# MGT.net
KiCad netlist of a schematic drawn in Altium Designer
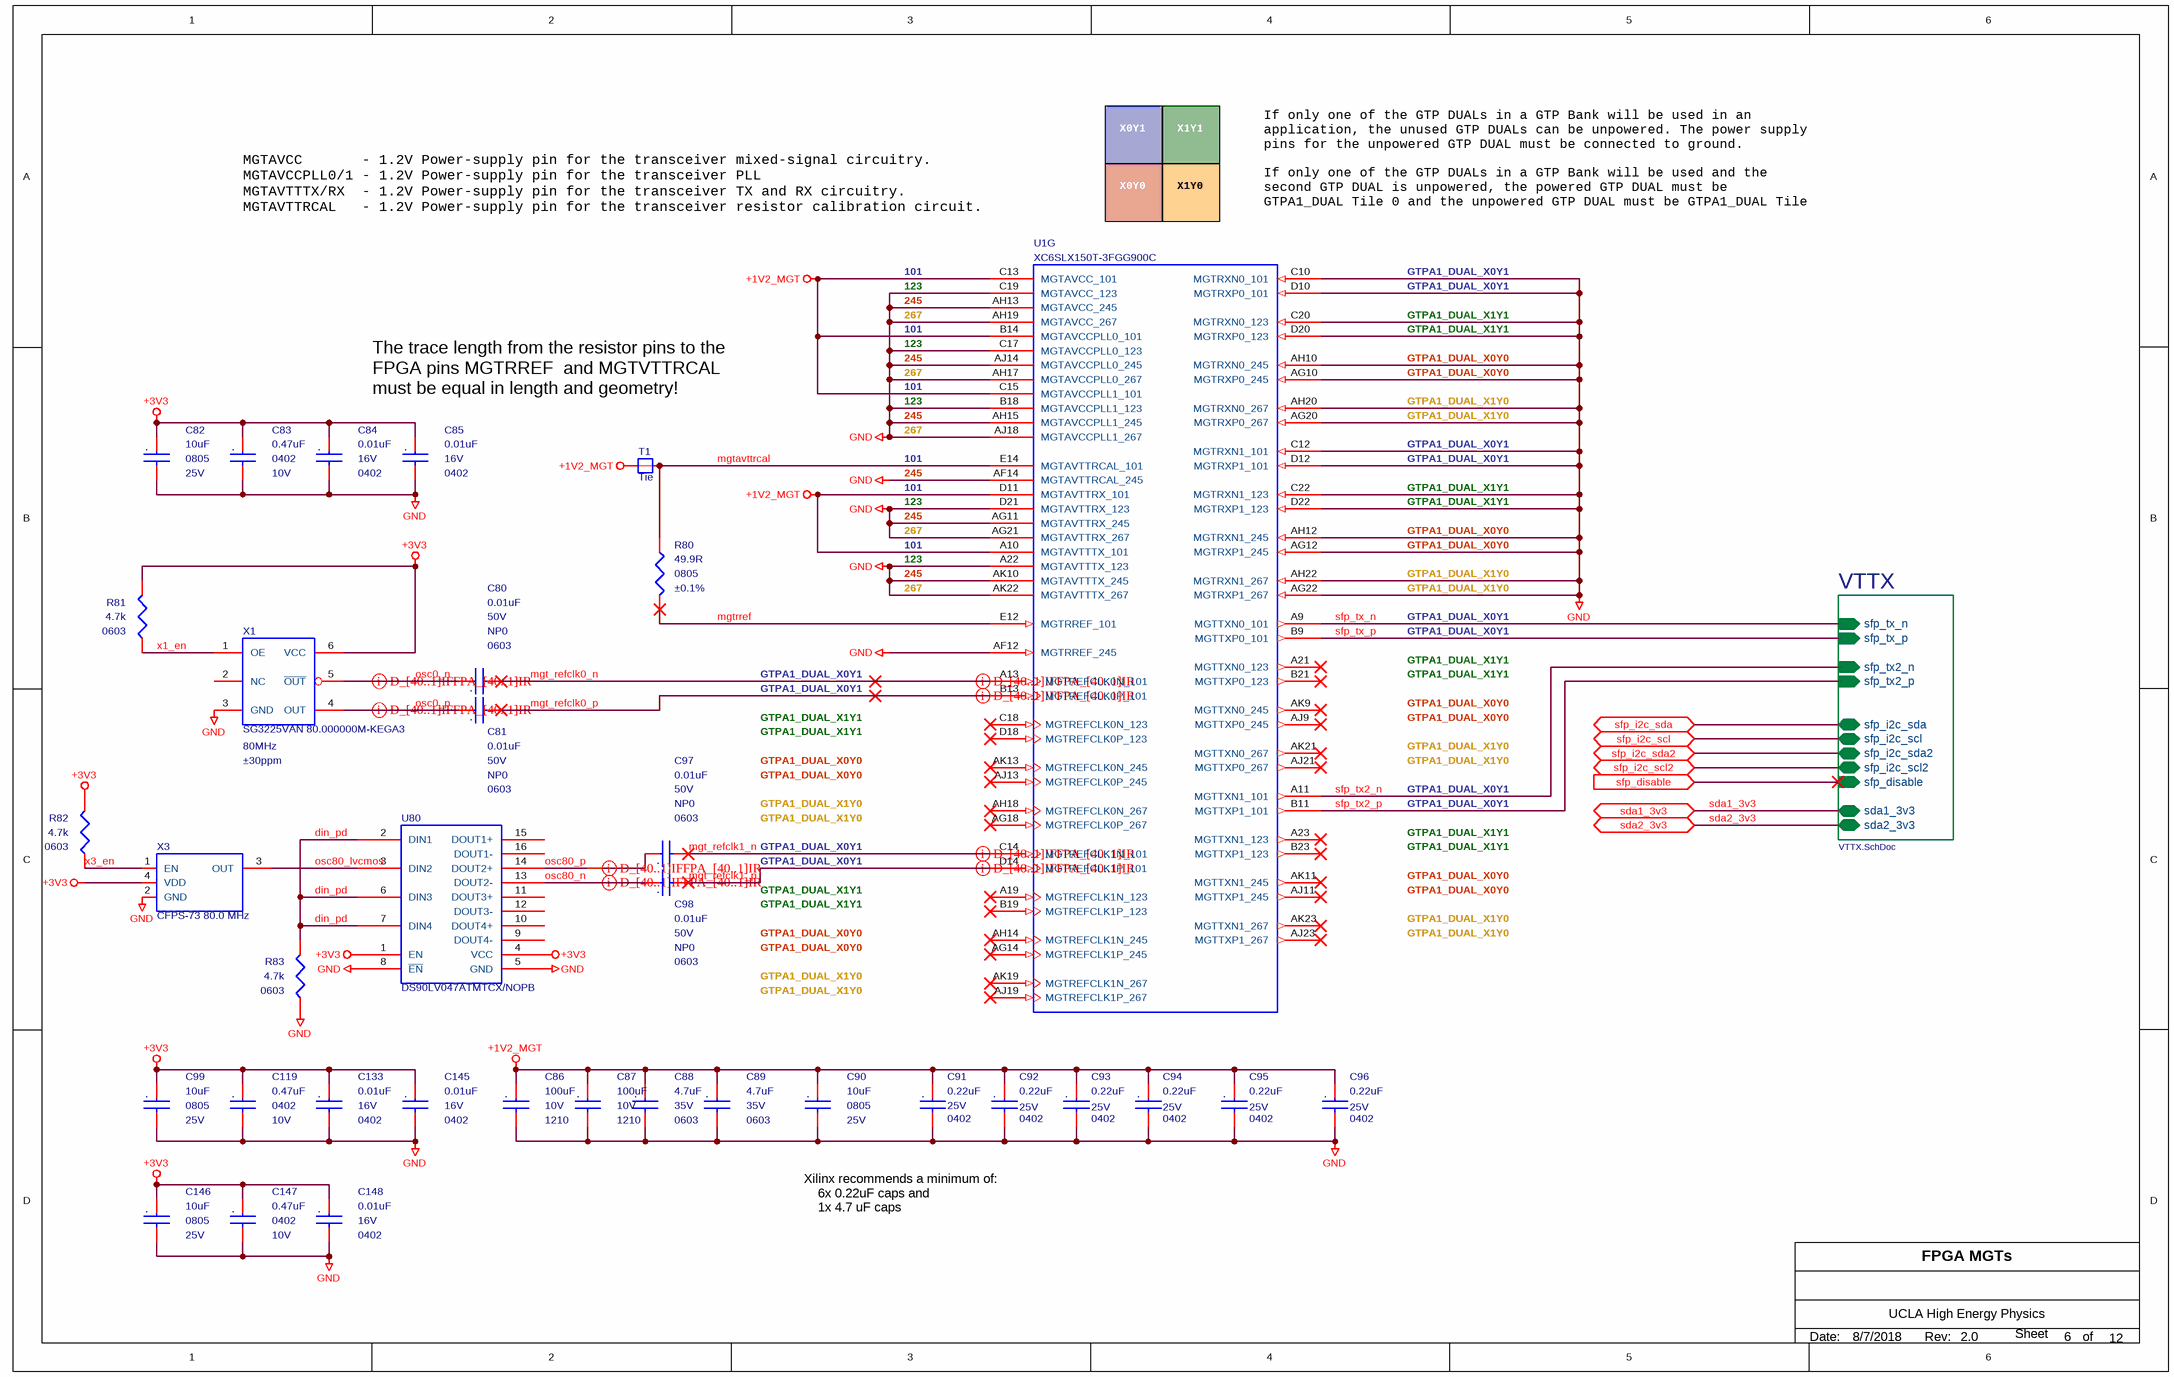
[diagram p0: MGT.SchDoc]

(export (version "E")
  (design (tool "Eeschema 10.0.6"))
  (components
    (comp (ref "C80")
      (value "0.01uF")
      (footprint "MC_S6/SM/C_0603_IPC")
      (description "CAP CER 10000PF 50V NP0 0603")
      (fields
        (field (name "MANUFACTURER") "KEMET")
        (field (name "MANUFACTURER PART NUMBER") "C0603C103J3GACTU")
        (field (name "TEMPERATURE COEFFICIENT") "NP0")
        (field (name "PACKAGE") "0603")
        (field (name "VOLTAGE - RATED") "50V")
      )
      (libsource (lib "ALCT_MEZ_SPARTAN6_Library") (part "C0603C103J3GACTU"))
    )
    (comp (ref "C81")
      (value "0.01uF")
      (footprint "MC_S6/SM/C_0603_IPC")
      (description "CAP CER 10000PF 50V NP0 0603")
      (fields
        (field (name "MANUFACTURER") "KEMET")
        (field (name "MANUFACTURER PART NUMBER") "C0603C103J3GACTU")
        (field (name "TEMPERATURE COEFFICIENT") "NP0")
        (field (name "PACKAGE") "0603")
        (field (name "VOLTAGE - RATED") "50V")
      )
      (libsource (lib "ALCT_MEZ_SPARTAN6_Library") (part "C0603C103J3GACTU"))
    )
    (comp (ref "C82")
      (value "10uF")
      (footprint "MC_S6/SM/C_0805_IPC")
      (description "CAP CER 10UF 25V X5R 0805")
      (fields
        (field (name "MANUFACTURER") "Murata Electronics North America")
        (field (name "MANUFACTURER PART NUMBER") "GRM21BR61E106KA73L")
        (field (name "VOLTAGE - RATED") "25V")
        (field (name "PACKAGE") "0805")
      )
      (libsource (lib "ALCT_MEZ_SPARTAN6_Library") (part "GRM21BR61E106KA73L"))
    )
    (comp (ref "C83")
      (value "0.47uF")
      (footprint "MC_S6/SM/C_0402_IPC")
      (description "CAP CER 0.47UF 10V X5R 0402")
      (fields
        (field (name "MANUFACTURER") "Murata Electronics North America")
        (field (name "MANUFACTURER PART NUMBER") "GRM155R61A474KE15J")
        (field (name "VOLTAGE - RATED") "10V")
        (field (name "PACKAGE") "0402")
      )
      (libsource (lib "ALCT_MEZ_SPARTAN6_Library") (part "GRM155R61A474KE15J"))
    )
    (comp (ref "C84")
      (value "0.01uF")
      (footprint "MC_S6/SM/C_0402_IPC")
      (description "CAP CER 10nF 16V X7R 0402")
      (fields
        (field (name "MANUFACTURER") "KEMET")
        (field (name "MANUFACTURER PART NUMBER") "C0402C103K4RACTU")
        (field (name "VOLTAGE - RATED") "16V")
        (field (name "PACKAGE") "0402")
      )
      (libsource (lib "ALCT_MEZ_SPARTAN6_Library") (part "C0402C103K4RACTU"))
    )
    (comp (ref "C85")
      (value "0.01uF")
      (footprint "MC_S6/SM/C_0402_IPC")
      (description "CAP CER 10nF 16V X7R 0402")
      (fields
        (field (name "MANUFACTURER") "KEMET")
        (field (name "MANUFACTURER PART NUMBER") "C0402C103K4RACTU")
        (field (name "VOLTAGE - RATED") "16V")
        (field (name "PACKAGE") "0402")
      )
      (libsource (lib "ALCT_MEZ_SPARTAN6_Library") (part "C0402C103K4RACTU"))
    )
    (comp (ref "C86")
      (value "100uF")
      (footprint "MC_S6/SM/C_1210_IPC")
      (description "CAP CER 100UF 10V X5R 1210")
      (fields
        (field (name "MANUFACTURER") "Taiyo Yuden")
        (field (name "MANUFACTURER PART NUMBER") "LMK325BJ107MM-T")
        (field (name "VOLTAGE - RATED") "10V")
        (field (name "PACKAGE") "1210")
      )
      (libsource (lib "ALCT_MEZ_SPARTAN6_Library") (part "LMK325BJ107MM-T"))
    )
    (comp (ref "C87")
      (value "100uF")
      (footprint "MC_S6/SM/C_1210_IPC")
      (description "CAP CER 100UF 10V X5R 1210")
      (fields
        (field (name "MANUFACTURER") "Taiyo Yuden")
        (field (name "MANUFACTURER PART NUMBER") "LMK325BJ107MM-T")
        (field (name "VOLTAGE - RATED") "10V")
        (field (name "PACKAGE") "1210")
      )
      (libsource (lib "ALCT_MEZ_SPARTAN6_Library") (part "LMK325BJ107MM-T"))
    )
    (comp (ref "C88")
      (value "4.7uF")
      (footprint "MC_S6/SM/C_0603_IPC")
      (description "CAP CER 4.7UF 35V X5R 0603")
      (fields
        (field (name "MANUFACTURER") "Murata")
        (field (name "MANUFACTURER PART NUMBER") "GRM188R6YA475KE15D")
        (field (name "VOLTAGE - RATED") "35V")
        (field (name "PACKAGE") "0603")
      )
      (libsource (lib "ALCT_MEZ_SPARTAN6_Library") (part "GRM188R6YA475KE15D"))
    )
    (comp (ref "C89")
      (value "4.7uF")
      (footprint "MC_S6/SM/C_0603_IPC")
      (description "CAP CER 4.7UF 35V X5R 0603")
      (fields
        (field (name "MANUFACTURER") "Murata")
        (field (name "MANUFACTURER PART NUMBER") "GRM188R6YA475KE15D")
        (field (name "VOLTAGE - RATED") "35V")
        (field (name "PACKAGE") "0603")
      )
      (libsource (lib "ALCT_MEZ_SPARTAN6_Library") (part "GRM188R6YA475KE15D"))
    )
    (comp (ref "C90")
      (value "10uF")
      (footprint "MC_S6/SM/C_0805_IPC")
      (description "CAP CER 10UF 25V X5R 0805")
      (fields
        (field (name "MANUFACTURER") "Murata Electronics North America")
        (field (name "MANUFACTURER PART NUMBER") "GRM21BR61E106KA73L")
        (field (name "VOLTAGE - RATED") "25V")
        (field (name "PACKAGE") "0805")
      )
      (libsource (lib "ALCT_MEZ_SPARTAN6_Library") (part "GRM21BR61E106KA73L"))
    )
    (comp (ref "C91")
      (value "0.22uF")
      (footprint "MC_S6/SM/C_0402_IPC")
      (description "CAP CER 0.22UF 15V X7R 0402")
      (fields
        (field (name "MANUFACTURER") "Murata Electronics North America")
        (field (name "MANUFACTURER PART NUMBER") "GRM155R71C224KA12D")
        (field (name "VOLTAGE - RATED") "25V")
        (field (name "PACKAGE") "0402")
      )
      (libsource (lib "ALCT_MEZ_SPARTAN6_Library") (part "GRM155R71C224KA12D"))
    )
    (comp (ref "C92")
      (value "0.22uF")
      (footprint "MC_S6/SM/C_0402_IPC")
      (description "CAP CER 0.22UF 15V X7R 0402")
      (fields
        (field (name "MANUFACTURER") "Murata Electronics North America")
        (field (name "MANUFACTURER PART NUMBER") "GRM155R71C224KA12D")
        (field (name "VOLTAGE - RATED") "25V")
        (field (name "PACKAGE") "0402")
      )
      (libsource (lib "ALCT_MEZ_SPARTAN6_Library") (part "GRM155R71C224KA12D"))
    )
    (comp (ref "C93")
      (value "0.22uF")
      (footprint "MC_S6/SM/C_0402_IPC")
      (description "CAP CER 0.22UF 15V X7R 0402")
      (fields
        (field (name "MANUFACTURER") "Murata Electronics North America")
        (field (name "MANUFACTURER PART NUMBER") "GRM155R71C224KA12D")
        (field (name "VOLTAGE - RATED") "25V")
        (field (name "PACKAGE") "0402")
      )
      (libsource (lib "ALCT_MEZ_SPARTAN6_Library") (part "GRM155R71C224KA12D"))
    )
    (comp (ref "C94")
      (value "0.22uF")
      (footprint "MC_S6/SM/C_0402_IPC")
      (description "CAP CER 0.22UF 15V X7R 0402")
      (fields
        (field (name "MANUFACTURER") "Murata Electronics North America")
        (field (name "MANUFACTURER PART NUMBER") "GRM155R71C224KA12D")
        (field (name "VOLTAGE - RATED") "25V")
        (field (name "PACKAGE") "0402")
      )
      (libsource (lib "ALCT_MEZ_SPARTAN6_Library") (part "GRM155R71C224KA12D"))
    )
    (comp (ref "C95")
      (value "0.22uF")
      (footprint "MC_S6/SM/C_0402_IPC")
      (description "CAP CER 0.22UF 15V X7R 0402")
      (fields
        (field (name "MANUFACTURER") "Murata Electronics North America")
        (field (name "MANUFACTURER PART NUMBER") "GRM155R71C224KA12D")
        (field (name "VOLTAGE - RATED") "25V")
        (field (name "PACKAGE") "0402")
      )
      (libsource (lib "ALCT_MEZ_SPARTAN6_Library") (part "GRM155R71C224KA12D"))
    )
    (comp (ref "C96")
      (value "0.22uF")
      (footprint "MC_S6/SM/C_0402_IPC")
      (description "CAP CER 0.22UF 15V X7R 0402")
      (fields
        (field (name "MANUFACTURER") "Murata Electronics North America")
        (field (name "MANUFACTURER PART NUMBER") "GRM155R71C224KA12D")
        (field (name "VOLTAGE - RATED") "25V")
        (field (name "PACKAGE") "0402")
      )
      (libsource (lib "ALCT_MEZ_SPARTAN6_Library") (part "GRM155R71C224KA12D"))
    )
    (comp (ref "C97")
      (value "0.01uF")
      (footprint "MC_S6/SM/C_0603_IPC")
      (description "CAP CER 10000PF 50V NP0 0603")
      (fields
        (field (name "MANUFACTURER") "KEMET")
        (field (name "MANUFACTURER PART NUMBER") "C0603C103J3GACTU")
        (field (name "TEMPERATURE COEFFICIENT") "NP0")
        (field (name "PACKAGE") "0603")
        (field (name "VOLTAGE - RATED") "50V")
      )
      (libsource (lib "ALCT_MEZ_SPARTAN6_Library") (part "C0603C103J3GACTU"))
    )
    (comp (ref "C98")
      (value "0.01uF")
      (footprint "MC_S6/SM/C_0603_IPC")
      (description "CAP CER 10000PF 50V NP0 0603")
      (fields
        (field (name "MANUFACTURER") "KEMET")
        (field (name "MANUFACTURER PART NUMBER") "C0603C103J3GACTU")
        (field (name "TEMPERATURE COEFFICIENT") "NP0")
        (field (name "PACKAGE") "0603")
        (field (name "VOLTAGE - RATED") "50V")
      )
      (libsource (lib "ALCT_MEZ_SPARTAN6_Library") (part "C0603C103J3GACTU"))
    )
    (comp (ref "C99")
      (value "10uF")
      (footprint "MC_S6/SM/C_0805_IPC")
      (description "CAP CER 10UF 25V X5R 0805")
      (fields
        (field (name "MANUFACTURER") "Murata Electronics North America")
        (field (name "MANUFACTURER PART NUMBER") "GRM21BR61E106KA73L")
        (field (name "VOLTAGE - RATED") "25V")
        (field (name "PACKAGE") "0805")
      )
      (libsource (lib "ALCT_MEZ_SPARTAN6_Library") (part "GRM21BR61E106KA73L"))
    )
    (comp (ref "C119")
      (value "0.47uF")
      (footprint "MC_S6/SM/C_0402_IPC")
      (description "CAP CER 0.47UF 10V X5R 0402")
      (fields
        (field (name "MANUFACTURER") "Murata Electronics North America")
        (field (name "MANUFACTURER PART NUMBER") "GRM155R61A474KE15J")
        (field (name "VOLTAGE - RATED") "10V")
        (field (name "PACKAGE") "0402")
      )
      (libsource (lib "ALCT_MEZ_SPARTAN6_Library") (part "GRM155R61A474KE15J"))
    )
    (comp (ref "C133")
      (value "0.01uF")
      (footprint "MC_S6/SM/C_0402_IPC")
      (description "CAP CER 10nF 16V X7R 0402")
      (fields
        (field (name "MANUFACTURER") "KEMET")
        (field (name "MANUFACTURER PART NUMBER") "C0402C103K4RACTU")
        (field (name "VOLTAGE - RATED") "16V")
        (field (name "PACKAGE") "0402")
      )
      (libsource (lib "ALCT_MEZ_SPARTAN6_Library") (part "C0402C103K4RACTU"))
    )
    (comp (ref "C145")
      (value "0.01uF")
      (footprint "MC_S6/SM/C_0402_IPC")
      (description "CAP CER 10nF 16V X7R 0402")
      (fields
        (field (name "MANUFACTURER") "KEMET")
        (field (name "MANUFACTURER PART NUMBER") "C0402C103K4RACTU")
        (field (name "VOLTAGE - RATED") "16V")
        (field (name "PACKAGE") "0402")
      )
      (libsource (lib "ALCT_MEZ_SPARTAN6_Library") (part "C0402C103K4RACTU"))
    )
    (comp (ref "C146")
      (value "10uF")
      (footprint "MC_S6/SM/C_0805_IPC")
      (description "CAP CER 10UF 25V X5R 0805")
      (fields
        (field (name "MANUFACTURER") "Murata Electronics North America")
        (field (name "MANUFACTURER PART NUMBER") "GRM21BR61E106KA73L")
        (field (name "VOLTAGE - RATED") "25V")
        (field (name "PACKAGE") "0805")
      )
      (libsource (lib "ALCT_MEZ_SPARTAN6_Library") (part "GRM21BR61E106KA73L"))
    )
    (comp (ref "C147")
      (value "0.47uF")
      (footprint "MC_S6/SM/C_0402_IPC")
      (description "CAP CER 0.47UF 10V X5R 0402")
      (fields
        (field (name "MANUFACTURER") "Murata Electronics North America")
        (field (name "MANUFACTURER PART NUMBER") "GRM155R61A474KE15J")
        (field (name "VOLTAGE - RATED") "10V")
        (field (name "PACKAGE") "0402")
      )
      (libsource (lib "ALCT_MEZ_SPARTAN6_Library") (part "GRM155R61A474KE15J"))
    )
    (comp (ref "C148")
      (value "0.01uF")
      (footprint "MC_S6/SM/C_0402_IPC")
      (description "CAP CER 10nF 16V X7R 0402")
      (fields
        (field (name "MANUFACTURER") "KEMET")
        (field (name "MANUFACTURER PART NUMBER") "C0402C103K4RACTU")
        (field (name "VOLTAGE - RATED") "16V")
        (field (name "PACKAGE") "0402")
      )
      (libsource (lib "ALCT_MEZ_SPARTAN6_Library") (part "C0402C103K4RACTU"))
    )
    (comp (ref "R80")
      (value "49.9R")
      (footprint "MC_S6/SM/R_0805_IPC")
      (description "RES SMD 49.9 OHM 0.1% 1/8W 0805")
      (fields
        (field (name "MANUFACTURER") "Panasonic Electronic Components")
        (field (name "MANUFACTURER PART NUMBER") "ERA-6AEB49R9V")
        (field (name "TOLERANCE") "±0.1%")
        (field (name "SUPPLIER DEVICE PACKAGE") "0805")
      )
      (libsource (lib "ALCT_MEZ_SPARTAN6_Library") (part "ERA-6AEB49R9V"))
    )
    (comp (ref "R81")
      (value "4.7k")
      (footprint "MC_S6/SM/R_0603_IPC")
      (description "RES SMD 4.7K OHM 1% 1/10W 0603")
      (fields
        (field (name "MANUFACTURER") "Bourns Inc.")
        (field (name "MANUFACTURER PART NUMBER") "CR0603-FX-4701ELF")
        (field (name "SUPPLIER DEVICE PACKAGE") "0603")
      )
      (libsource (lib "ALCT_MEZ_SPARTAN6_Library") (part "CR0603-FX-4701ELF"))
    )
    (comp (ref "R82")
      (value "4.7k")
      (footprint "MC_S6/SM/R_0603_IPC")
      (description "RES SMD 4.7K OHM 1% 1/10W 0603")
      (fields
        (field (name "MANUFACTURER") "Bourns Inc.")
        (field (name "MANUFACTURER PART NUMBER") "CR0603-FX-4701ELF")
        (field (name "SUPPLIER DEVICE PACKAGE") "0603")
      )
      (libsource (lib "ALCT_MEZ_SPARTAN6_Library") (part "CR0603-FX-4701ELF"))
    )
    (comp (ref "R83")
      (value "4.7k")
      (footprint "MC_S6/SM/R_0603_IPC")
      (description "RES SMD 4.7K OHM 1% 1/10W 0603")
      (fields
        (field (name "MANUFACTURER") "Bourns Inc.")
        (field (name "MANUFACTURER PART NUMBER") "CR0603-FX-4701ELF")
        (field (name "SUPPLIER DEVICE PACKAGE") "0603")
      )
      (libsource (lib "ALCT_MEZ_SPARTAN6_Library") (part "CR0603-FX-4701ELF"))
    )
    (comp (ref "T1")
      (value "Tie")
      (footprint "MC_S6/TH/TIE_VIA")
      (libsource (lib "ALCT_MEZ_SPARTAN6_Library") (part "NET TIE VIA"))
    )
    (comp (ref "U1")
      (value "XC6SLX150T-3FGG900C")
      (footprint "MC_S6/BGA/FGG900")
      (fields (field (name "MANUFACTURER") "Xilinx Inc."))
      (libsource (lib "ALCT_MEZ_SPARTAN6_Library") (part "XC6SLX150T-3FGG900C"))
    )
    (comp (ref "U80")
      (value "DS90LV047ATMTCX/NOPB")
      (footprint "MC_S6/SM/TSSOP16")
      (description "IC LINE DVR 3V QUAD DIFF 16TSSOP")
      (fields (field (name "MANUFACTURER") "TI National Semiconductor"))
      (libsource (lib "ALCT_MEZ_SPARTAN6_Library") (part "DS90LV047ATMTCX"))
    )
    (comp (ref "X1")
      (value "SG3225VAN 80.000000M-KEGA3")
      (footprint "MC_S6/SM/XTAL-LVDS-3.2-2.5")
      (description "OSC 80.0000MHZ LVDS SMD")
      (fields
        (field (name "MANUFACTURER") "EPSON")
        (field (name "FREQUENCY") "80MHz")
        (field (name "FREQUENCY STABILITY") "±30ppm")
      )
      (libsource (lib "ALCT_MEZ_SPARTAN6_Library") (part "SG3225VAN 80.000000M-KEGA3"))
    )
    (comp (ref "X3")
      (value "CFPS-73 80.0 MHz")
      (footprint "MC_S6/SM/XTAL-7x5.08")
      (description "XTAL, 80MHz, CMOS")
      (fields
        (field (name "MANUFACTURER") "IQD")
        (field (name "MANUFACTURER PART NUMBER") "LFSPXO009441REEL")
      )
      (libsource (lib "ALCT_MEZ_SPARTAN6_Library") (part "LFSPXO009441"))
    )
  )
  (nets
    (net (code "1") (name "+1V2_MGT") (class "Default")
      (node (ref "C86") (pin "1") (pinfunction "1_1") (pintype "passive"))
      (node (ref "C87") (pin "1") (pinfunction "1_1") (pintype "passive"))
      (node (ref "C88") (pin "1") (pinfunction "1_1") (pintype "passive"))
      (node (ref "C89") (pin "1") (pinfunction "1_1") (pintype "passive"))
      (node (ref "C90") (pin "1") (pinfunction "1_1") (pintype "passive"))
      (node (ref "C91") (pin "1") (pinfunction "1_1") (pintype "passive"))
      (node (ref "C92") (pin "1") (pinfunction "1_1") (pintype "passive"))
      (node (ref "C93") (pin "1") (pinfunction "1_1") (pintype "passive"))
      (node (ref "C94") (pin "1") (pinfunction "1_1") (pintype "passive"))
      (node (ref "C95") (pin "1") (pinfunction "1_1") (pintype "passive"))
      (node (ref "C96") (pin "1") (pinfunction "1_1") (pintype "passive"))
      (node (ref "T1") (pin "2") (pinfunction "2_2") (pintype "passive"))
      (node (ref "U1") (pin "A10") (pinfunction "MGTAVTTTX_101_A10") (pintype "power_in"))
      (node (ref "U1") (pin "B14") (pinfunction "MGTAVCCPLL0_101_B14") (pintype "power_in"))
      (node (ref "U1") (pin "C13") (pinfunction "MGTAVCC_101_C13") (pintype "power_in"))
      (node (ref "U1") (pin "C15") (pinfunction "MGTAVCCPLL1_101_C15") (pintype "power_in"))
      (node (ref "U1") (pin "D11") (pinfunction "MGTAVTTRX_101_D11") (pintype "power_in"))
    )
    (net (code "2") (name "+3V3") (class "Default")
      (node (ref "C119") (pin "1") (pinfunction "1_1") (pintype "passive"))
      (node (ref "C133") (pin "1") (pinfunction "1_1") (pintype "passive"))
      (node (ref "C145") (pin "1") (pinfunction "1_1") (pintype "passive"))
      (node (ref "C146") (pin "1") (pinfunction "1_1") (pintype "passive"))
      (node (ref "C147") (pin "1") (pinfunction "1_1") (pintype "passive"))
      (node (ref "C148") (pin "1") (pinfunction "1_1") (pintype "passive"))
      (node (ref "C82") (pin "1") (pinfunction "1_1") (pintype "passive"))
      (node (ref "C83") (pin "1") (pinfunction "1_1") (pintype "passive"))
      (node (ref "C84") (pin "1") (pinfunction "1_1") (pintype "passive"))
      (node (ref "C85") (pin "1") (pinfunction "1_1") (pintype "passive"))
      (node (ref "C99") (pin "1") (pinfunction "1_1") (pintype "passive"))
      (node (ref "R81") (pin "1") (pinfunction "1_1") (pintype "passive"))
      (node (ref "R82") (pin "1") (pinfunction "1_1") (pintype "passive"))
      (node (ref "U80") (pin "1") (pinfunction "EN_1") (pintype "power_in"))
      (node (ref "U80") (pin "4") (pinfunction "VCC_4") (pintype "power_in"))
      (node (ref "X1") (pin "6") (pinfunction "VCC_6") (pintype "passive"))
      (node (ref "X3") (pin "4") (pinfunction "VDD_4") (pintype "passive"))
    )
    (net (code "3") (name "/din_pd") (class "Default")
      (node (ref "R83") (pin "1") (pinfunction "1_1") (pintype "passive"))
      (node (ref "U80") (pin "2") (pinfunction "DIN1_2") (pintype "power_in"))
      (node (ref "U80") (pin "6") (pinfunction "DIN3_6") (pintype "power_in"))
      (node (ref "U80") (pin "7") (pinfunction "DIN4_7") (pintype "power_in"))
    )
    (net (code "4") (name "/mgt_refclk0_n") (class "Default")
      (node (ref "C80") (pin "2") (pinfunction "2_2") (pintype "passive"))
      (node (ref "U1") (pin "A13") (pinfunction "MGTREFCLK0N_101_A13") (pintype "input"))
    )
    (net (code "5") (name "/mgt_refclk0_p") (class "Default")
      (node (ref "C81") (pin "2") (pinfunction "2_2") (pintype "passive"))
      (node (ref "U1") (pin "B13") (pinfunction "MGTREFCLK0P_101_B13") (pintype "input"))
    )
    (net (code "6") (name "/mgt_refclk1_n") (class "Default")
      (node (ref "C97") (pin "2") (pinfunction "2_2") (pintype "passive"))
      (node (ref "U1") (pin "C14") (pinfunction "MGTREFCLK1N_101_C14") (pintype "input"))
    )
    (net (code "7") (name "/mgt_refclk1_p") (class "Default")
      (node (ref "C98") (pin "2") (pinfunction "2_2") (pintype "passive"))
      (node (ref "U1") (pin "D14") (pinfunction "MGTREFCLK1P_101_D14") (pintype "input"))
    )
    (net (code "8") (name "/mgtavttrcal") (class "Default")
      (node (ref "R80") (pin "1") (pinfunction "1_1") (pintype "passive"))
      (node (ref "T1") (pin "1") (pinfunction "1_1") (pintype "passive"))
      (node (ref "U1") (pin "E14") (pinfunction "MGTAVTTRCAL_101_E14") (pintype "power_in"))
    )
    (net (code "9") (name "/mgtrref") (class "Default")
      (node (ref "R80") (pin "2") (pinfunction "2_2") (pintype "passive"))
      (node (ref "U1") (pin "E12") (pinfunction "MGTRREF_101_E12") (pintype "input"))
    )
    (net (code "10") (name "/osc0_n") (class "Default")
      (node (ref "C80") (pin "1") (pinfunction "1_1") (pintype "passive"))
      (node (ref "X1") (pin "5") (pinfunction "~{OUT}_5") (pintype "passive"))
    )
    (net (code "11") (name "/osc0_p") (class "Default")
      (node (ref "C81") (pin "1") (pinfunction "1_1") (pintype "passive"))
      (node (ref "X1") (pin "4") (pinfunction "OUT_4") (pintype "passive"))
    )
    (net (code "12") (name "/osc80_lvcmos") (class "Default")
      (node (ref "U80") (pin "3") (pinfunction "DIN2_3") (pintype "power_in"))
      (node (ref "X3") (pin "3") (pinfunction "OUT_3") (pintype "passive"))
    )
    (net (code "13") (name "/osc80_n") (class "Default")
      (node (ref "C98") (pin "1") (pinfunction "1_1") (pintype "passive"))
      (node (ref "U80") (pin "13") (pinfunction "DOUT2-_13") (pintype "power_in"))
    )
    (net (code "14") (name "/osc80_p") (class "Default")
      (node (ref "C97") (pin "1") (pinfunction "1_1") (pintype "passive"))
      (node (ref "U80") (pin "14") (pinfunction "DOUT2+_14") (pintype "power_in"))
    )
    (net (code "22") (name "/sfp_tx2_n") (class "Default")
      (node (ref "U1") (pin "A11") (pinfunction "MGTTXN1_101_A11") (pintype "output"))
    )
    (net (code "23") (name "/sfp_tx2_p") (class "Default")
      (node (ref "U1") (pin "B11") (pinfunction "MGTTXP1_101_B11") (pintype "output"))
    )
    (net (code "24") (name "/sfp_tx_n") (class "Default")
      (node (ref "U1") (pin "A9") (pinfunction "MGTTXN0_101_A9") (pintype "output"))
    )
    (net (code "25") (name "/sfp_tx_p") (class "Default")
      (node (ref "U1") (pin "B9") (pinfunction "MGTTXP0_101_B9") (pintype "output"))
    )
    (net (code "26") (name "/x1_en") (class "Default")
      (node (ref "R81") (pin "2") (pinfunction "2_2") (pintype "passive"))
      (node (ref "X1") (pin "1") (pinfunction "OE_1") (pintype "passive"))
    )
    (net (code "27") (name "/x3_en") (class "Default")
      (node (ref "R82") (pin "2") (pinfunction "2_2") (pintype "passive"))
      (node (ref "X3") (pin "1") (pinfunction "EN_1") (pintype "passive"))
    )
    (net (code "28") (name "GND") (class "Default")
      (node (ref "C119") (pin "2") (pinfunction "2_2") (pintype "passive"))
      (node (ref "C133") (pin "2") (pinfunction "2_2") (pintype "passive"))
      (node (ref "C145") (pin "2") (pinfunction "2_2") (pintype "passive"))
      (node (ref "C146") (pin "2") (pinfunction "2_2") (pintype "passive"))
      (node (ref "C147") (pin "2") (pinfunction "2_2") (pintype "passive"))
      (node (ref "C148") (pin "2") (pinfunction "2_2") (pintype "passive"))
      (node (ref "C82") (pin "2") (pinfunction "2_2") (pintype "passive"))
      (node (ref "C83") (pin "2") (pinfunction "2_2") (pintype "passive"))
      (node (ref "C84") (pin "2") (pinfunction "2_2") (pintype "passive"))
      (node (ref "C85") (pin "2") (pinfunction "2_2") (pintype "passive"))
      (node (ref "C86") (pin "2") (pinfunction "2_2") (pintype "passive"))
      (node (ref "C87") (pin "2") (pinfunction "2_2") (pintype "passive"))
      (node (ref "C88") (pin "2") (pinfunction "2_2") (pintype "passive"))
      (node (ref "C89") (pin "2") (pinfunction "2_2") (pintype "passive"))
      (node (ref "C90") (pin "2") (pinfunction "2_2") (pintype "passive"))
      (node (ref "C91") (pin "2") (pinfunction "2_2") (pintype "passive"))
      (node (ref "C92") (pin "2") (pinfunction "2_2") (pintype "passive"))
      (node (ref "C93") (pin "2") (pinfunction "2_2") (pintype "passive"))
      (node (ref "C94") (pin "2") (pinfunction "2_2") (pintype "passive"))
      (node (ref "C95") (pin "2") (pinfunction "2_2") (pintype "passive"))
      (node (ref "C96") (pin "2") (pinfunction "2_2") (pintype "passive"))
      (node (ref "C99") (pin "2") (pinfunction "2_2") (pintype "passive"))
      (node (ref "R83") (pin "2") (pinfunction "2_2") (pintype "passive"))
      (node (ref "U1") (pin "A22") (pinfunction "MGTAVTTTX_123_A22") (pintype "power_in"))
      (node (ref "U1") (pin "AF12") (pinfunction "MGTRREF_245_AF12") (pintype "input"))
      (node (ref "U1") (pin "AF14") (pinfunction "MGTAVTTRCAL_245_AF14") (pintype "power_in"))
      (node (ref "U1") (pin "AG10") (pinfunction "MGTRXP0_245_AG10") (pintype "input"))
      (node (ref "U1") (pin "AG11") (pinfunction "MGTAVTTRX_245_AG11") (pintype "power_in"))
      (node (ref "U1") (pin "AG12") (pinfunction "MGTRXP1_245_AG12") (pintype "input"))
      (node (ref "U1") (pin "AG20") (pinfunction "MGTRXP0_267_AG20") (pintype "input"))
      (node (ref "U1") (pin "AG21") (pinfunction "MGTAVTTRX_267_AG21") (pintype "power_in"))
      (node (ref "U1") (pin "AG22") (pinfunction "MGTRXP1_267_AG22") (pintype "input"))
      (node (ref "U1") (pin "AH10") (pinfunction "MGTRXN0_245_AH10") (pintype "input"))
      (node (ref "U1") (pin "AH12") (pinfunction "MGTRXN1_245_AH12") (pintype "input"))
      (node (ref "U1") (pin "AH13") (pinfunction "MGTAVCC_245_AH13") (pintype "power_in"))
      (node (ref "U1") (pin "AH15") (pinfunction "MGTAVCCPLL1_245_AH15") (pintype "power_in"))
      (node (ref "U1") (pin "AH17") (pinfunction "MGTAVCCPLL0_267_AH17") (pintype "power_in"))
      (node (ref "U1") (pin "AH19") (pinfunction "MGTAVCC_267_AH19") (pintype "power_in"))
      (node (ref "U1") (pin "AH20") (pinfunction "MGTRXN0_267_AH20") (pintype "input"))
      (node (ref "U1") (pin "AH22") (pinfunction "MGTRXN1_267_AH22") (pintype "input"))
      (node (ref "U1") (pin "AJ14") (pinfunction "MGTAVCCPLL0_245_AJ14") (pintype "power_in"))
      (node (ref "U1") (pin "AJ18") (pinfunction "MGTAVCCPLL1_267_AJ18") (pintype "power_in"))
      (node (ref "U1") (pin "AK10") (pinfunction "MGTAVTTTX_245_AK10") (pintype "power_in"))
      (node (ref "U1") (pin "AK22") (pinfunction "MGTAVTTTX_267_AK22") (pintype "power_in"))
      (node (ref "U1") (pin "B18") (pinfunction "MGTAVCCPLL1_123_B18") (pintype "power_in"))
      (node (ref "U1") (pin "C10") (pinfunction "MGTRXN0_101_C10") (pintype "input"))
      (node (ref "U1") (pin "C12") (pinfunction "MGTRXN1_101_C12") (pintype "input"))
      (node (ref "U1") (pin "C17") (pinfunction "MGTAVCCPLL0_123_C17") (pintype "power_in"))
      (node (ref "U1") (pin "C19") (pinfunction "MGTAVCC_123_C19") (pintype "power_in"))
      (node (ref "U1") (pin "C20") (pinfunction "MGTRXN0_123_C20") (pintype "input"))
      (node (ref "U1") (pin "C22") (pinfunction "MGTRXN1_123_C22") (pintype "input"))
      (node (ref "U1") (pin "D10") (pinfunction "MGTRXP0_101_D10") (pintype "input"))
      (node (ref "U1") (pin "D12") (pinfunction "MGTRXP1_101_D12") (pintype "input"))
      (node (ref "U1") (pin "D20") (pinfunction "MGTRXP0_123_D20") (pintype "input"))
      (node (ref "U1") (pin "D21") (pinfunction "MGTAVTTRX_123_D21") (pintype "power_in"))
      (node (ref "U1") (pin "D22") (pinfunction "MGTRXP1_123_D22") (pintype "input"))
      (node (ref "U80") (pin "5") (pinfunction "GND_5") (pintype "power_in"))
      (node (ref "U80") (pin "8") (pinfunction "~{EN}_8") (pintype "power_in"))
      (node (ref "X1") (pin "3") (pinfunction "GND_3") (pintype "passive"))
      (node (ref "X3") (pin "2") (pinfunction "GND_2") (pintype "passive"))
    )
    (net (code "29") (name "unconnected-(U1G-MGTREFCLK0N_123-PadC18)") (class "Default")
      (node (ref "U1") (pin "C18") (pinfunction "MGTREFCLK0N_123_C18") (pintype "input+no_connect"))
    )
    (net (code "30") (name "unconnected-(U1G-MGTREFCLK0N_245-PadAK13)") (class "Default")
      (node (ref "U1") (pin "AK13") (pinfunction "MGTREFCLK0N_245_AK13") (pintype "input+no_connect"))
    )
    (net (code "31") (name "unconnected-(U1G-MGTREFCLK0N_267-PadAH18)") (class "Default")
      (node (ref "U1") (pin "AH18") (pinfunction "MGTREFCLK0N_267_AH18") (pintype "input+no_connect"))
    )
    (net (code "32") (name "unconnected-(U1G-MGTREFCLK0P_123-PadD18)") (class "Default")
      (node (ref "U1") (pin "D18") (pinfunction "MGTREFCLK0P_123_D18") (pintype "input+no_connect"))
    )
    (net (code "33") (name "unconnected-(U1G-MGTREFCLK0P_245-PadAJ13)") (class "Default")
      (node (ref "U1") (pin "AJ13") (pinfunction "MGTREFCLK0P_245_AJ13") (pintype "input+no_connect"))
    )
    (net (code "34") (name "unconnected-(U1G-MGTREFCLK0P_267-PadAG18)") (class "Default")
      (node (ref "U1") (pin "AG18") (pinfunction "MGTREFCLK0P_267_AG18") (pintype "input+no_connect"))
    )
    (net (code "35") (name "unconnected-(U1G-MGTREFCLK1N_123-PadA19)") (class "Default")
      (node (ref "U1") (pin "A19") (pinfunction "MGTREFCLK1N_123_A19") (pintype "input+no_connect"))
    )
    (net (code "36") (name "unconnected-(U1G-MGTREFCLK1N_245-PadAH14)") (class "Default")
      (node (ref "U1") (pin "AH14") (pinfunction "MGTREFCLK1N_245_AH14") (pintype "input+no_connect"))
    )
    (net (code "37") (name "unconnected-(U1G-MGTREFCLK1N_267-PadAK19)") (class "Default")
      (node (ref "U1") (pin "AK19") (pinfunction "MGTREFCLK1N_267_AK19") (pintype "input+no_connect"))
    )
    (net (code "38") (name "unconnected-(U1G-MGTREFCLK1P_123-PadB19)") (class "Default")
      (node (ref "U1") (pin "B19") (pinfunction "MGTREFCLK1P_123_B19") (pintype "input+no_connect"))
    )
    (net (code "39") (name "unconnected-(U1G-MGTREFCLK1P_245-PadAG14)") (class "Default")
      (node (ref "U1") (pin "AG14") (pinfunction "MGTREFCLK1P_245_AG14") (pintype "input+no_connect"))
    )
    (net (code "40") (name "unconnected-(U1G-MGTREFCLK1P_267-PadAJ19)") (class "Default")
      (node (ref "U1") (pin "AJ19") (pinfunction "MGTREFCLK1P_267_AJ19") (pintype "input+no_connect"))
    )
    (net (code "41") (name "unconnected-(U1G-MGTTXN0_123-PadA21)") (class "Default")
      (node (ref "U1") (pin "A21") (pinfunction "MGTTXN0_123_A21") (pintype "output+no_connect"))
    )
    (net (code "42") (name "unconnected-(U1G-MGTTXN0_245-PadAK9)") (class "Default")
      (node (ref "U1") (pin "AK9") (pinfunction "MGTTXN0_245_AK9") (pintype "output+no_connect"))
    )
    (net (code "43") (name "unconnected-(U1G-MGTTXN0_267-PadAK21)") (class "Default")
      (node (ref "U1") (pin "AK21") (pinfunction "MGTTXN0_267_AK21") (pintype "output+no_connect"))
    )
    (net (code "44") (name "unconnected-(U1G-MGTTXN1_123-PadA23)") (class "Default")
      (node (ref "U1") (pin "A23") (pinfunction "MGTTXN1_123_A23") (pintype "output+no_connect"))
    )
    (net (code "45") (name "unconnected-(U1G-MGTTXN1_245-PadAK11)") (class "Default")
      (node (ref "U1") (pin "AK11") (pinfunction "MGTTXN1_245_AK11") (pintype "output+no_connect"))
    )
    (net (code "46") (name "unconnected-(U1G-MGTTXN1_267-PadAK23)") (class "Default")
      (node (ref "U1") (pin "AK23") (pinfunction "MGTTXN1_267_AK23") (pintype "output+no_connect"))
    )
    (net (code "47") (name "unconnected-(U1G-MGTTXP0_123-PadB21)") (class "Default")
      (node (ref "U1") (pin "B21") (pinfunction "MGTTXP0_123_B21") (pintype "output+no_connect"))
    )
    (net (code "48") (name "unconnected-(U1G-MGTTXP0_245-PadAJ9)") (class "Default")
      (node (ref "U1") (pin "AJ9") (pinfunction "MGTTXP0_245_AJ9") (pintype "output+no_connect"))
    )
    (net (code "49") (name "unconnected-(U1G-MGTTXP0_267-PadAJ21)") (class "Default")
      (node (ref "U1") (pin "AJ21") (pinfunction "MGTTXP0_267_AJ21") (pintype "output+no_connect"))
    )
    (net (code "50") (name "unconnected-(U1G-MGTTXP1_123-PadB23)") (class "Default")
      (node (ref "U1") (pin "B23") (pinfunction "MGTTXP1_123_B23") (pintype "output+no_connect"))
    )
    (net (code "51") (name "unconnected-(U1G-MGTTXP1_245-PadAJ11)") (class "Default")
      (node (ref "U1") (pin "AJ11") (pinfunction "MGTTXP1_245_AJ11") (pintype "output+no_connect"))
    )
    (net (code "52") (name "unconnected-(U1G-MGTTXP1_267-PadAJ23)") (class "Default")
      (node (ref "U1") (pin "AJ23") (pinfunction "MGTTXP1_267_AJ23") (pintype "output+no_connect"))
    )
    (net (code "53") (name "unconnected-(U80-DOUT1+-Pad15)") (class "Default")
      (node (ref "U80") (pin "15") (pinfunction "DOUT1+_15") (pintype "power_in"))
    )
    (net (code "54") (name "unconnected-(U80-DOUT1--Pad16)") (class "Default")
      (node (ref "U80") (pin "16") (pinfunction "DOUT1-_16") (pintype "power_in"))
    )
    (net (code "55") (name "unconnected-(U80-DOUT3+-Pad11)") (class "Default")
      (node (ref "U80") (pin "11") (pinfunction "DOUT3+_11") (pintype "power_in"))
    )
    (net (code "56") (name "unconnected-(U80-DOUT3--Pad12)") (class "Default")
      (node (ref "U80") (pin "12") (pinfunction "DOUT3-_12") (pintype "power_in"))
    )
    (net (code "57") (name "unconnected-(U80-DOUT4+-Pad10)") (class "Default")
      (node (ref "U80") (pin "10") (pinfunction "DOUT4+_10") (pintype "power_in"))
    )
    (net (code "58") (name "unconnected-(U80-DOUT4--Pad9)") (class "Default")
      (node (ref "U80") (pin "9") (pinfunction "DOUT4-_9") (pintype "power_in"))
    )
    (net (code "59") (name "unconnected-(X1-NC-Pad2)") (class "Default")
      (node (ref "X1") (pin "2") (pinfunction "NC_2") (pintype "passive"))
    )
  )
)
